# STM32F103C8T61.net
KiCad netlist of a schematic drawn in Altium Designer
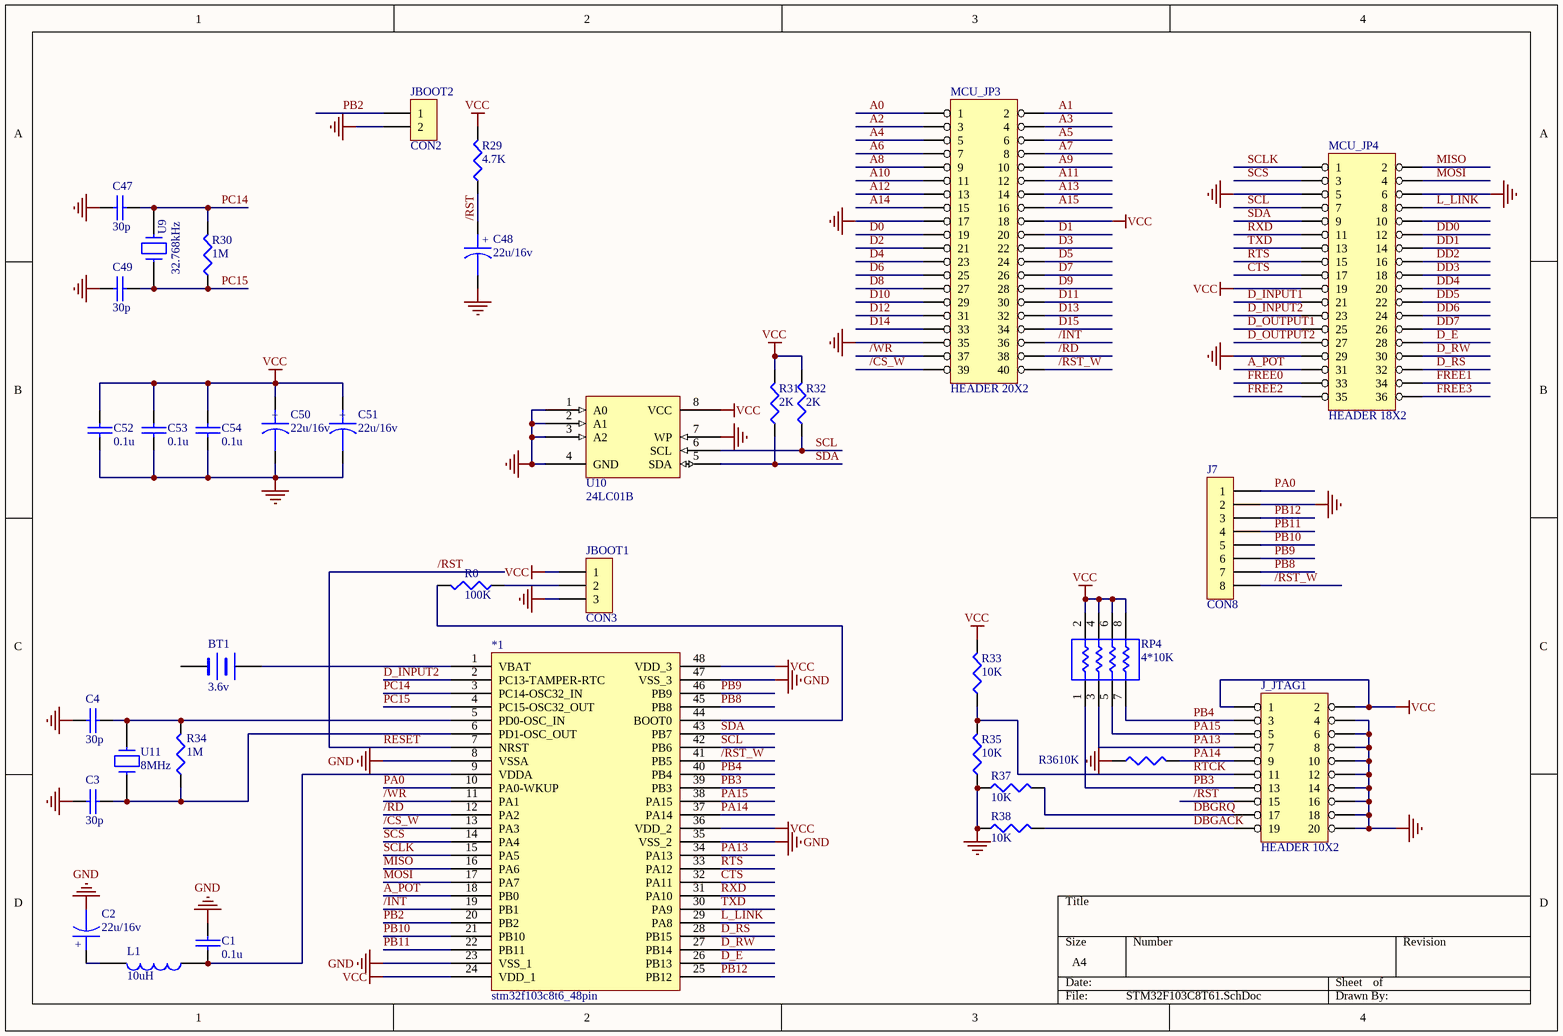
[diagram p0: STM32F103C8T61.SchDoc]

(export (version "E")
  (design (tool "Eeschema 10.0.6"))
  (components
    (comp (ref "*1") (value "stm32f103c8t6_48pin") (libsource (lib "stm32原理图库") (part "stm32f103c8t6_48pin")))
    (comp (ref "BT1")
      (value "3.6v")
      (footprint "BAT_JACK1")
      (description "Battery")
      (libsource (lib "*") (part "BATTERY"))
    )
    (comp (ref "C1")
      (value "0.1u")
      (footprint "0603")
      (description "Capacitor")
      (libsource (lib "*") (part "CAP"))
    )
    (comp (ref "C2")
      (value "22u/16v")
      (footprint "RB.1/.2N")
      (description "Capacitor")
      (libsource (lib "*") (part "CAPACITOR POL"))
    )
    (comp (ref "C3")
      (value "30p")
      (footprint "0603")
      (description "Capacitor")
      (libsource (lib "*") (part "CAP"))
    )
    (comp (ref "C4")
      (value "30p")
      (footprint "0603")
      (description "Capacitor")
      (libsource (lib "*") (part "CAP"))
    )
    (comp (ref "C47")
      (value "30p")
      (footprint "0603")
      (description "Capacitor")
      (libsource (lib "*") (part "CAP"))
    )
    (comp (ref "C48")
      (value "22u/16v")
      (footprint "RB.1/.2N")
      (description "Capacitor")
      (libsource (lib "*") (part "CAPACITOR POL"))
    )
    (comp (ref "C49")
      (value "30p")
      (footprint "0603")
      (description "Capacitor")
      (libsource (lib "*") (part "CAP"))
    )
    (comp (ref "C50")
      (value "22u/16v")
      (footprint "RB.1/.2N")
      (description "Capacitor")
      (libsource (lib "") (part "CAPACITOR POL_1"))
    )
    (comp (ref "C51")
      (value "22u/16v")
      (footprint "RB.1/.2N")
      (description "Capacitor")
      (libsource (lib "") (part "CAPACITOR POL_1"))
    )
    (comp (ref "C52")
      (value "0.1u")
      (footprint "0603")
      (description "Capacitor")
      (libsource (lib "*") (part "CAP"))
    )
    (comp (ref "C53")
      (value "0.1u")
      (footprint "0603")
      (description "Capacitor")
      (libsource (lib "*") (part "CAP"))
    )
    (comp (ref "C54")
      (value "0.1u")
      (footprint "0603")
      (description "Capacitor")
      (libsource (lib "*") (part "CAP"))
    )
    (comp (ref "J7")
      (value "CON8")
      (footprint "SIP8")
      (description "Connector")
      (libsource (lib "*") (part "CON8"))
    )
    (comp (ref "JBOOT1")
      (value "CON3")
      (footprint "SIP3")
      (description "Connector")
      (libsource (lib "*") (part "CON3"))
    )
    (comp (ref "JBOOT2")
      (value "CON2")
      (footprint "SIP2")
      (description "Connector")
      (libsource (lib "*") (part "CON2"))
    )
    (comp (ref "J_JTAG1")
      (value "HEADER 10X2")
      (footprint "IDC20")
      (libsource (lib "*") (part "HEADER 10X2"))
    )
    (comp (ref "L1") (value "10uH") (footprint "0603") (libsource (lib "*") (part "INDUCTOR")))
    (comp (ref "MCU_JP3")
      (value "HEADER 20X2")
      (footprint "IDC40-2")
      (libsource (lib "*") (part "HEADER 20X2"))
    )
    (comp (ref "MCU_JP4")
      (value "HEADER 18X2")
      (footprint "IDC36-2")
      (libsource (lib "*") (part "HEADER 18X2"))
    )
    (comp (ref "R0") (value "100K") (footprint "0603") (libsource (lib "*") (part "RES1")))
    (comp (ref "R29") (value "4.7K") (footprint "0603") (libsource (lib "*") (part "RES1")))
    (comp (ref "R30") (value "1M") (footprint "0603") (libsource (lib "*") (part "RES1")))
    (comp (ref "R31") (value "2K") (footprint "0603") (libsource (lib "*") (part "RES1")))
    (comp (ref "R32") (value "2K") (footprint "0603") (libsource (lib "*") (part "RES1")))
    (comp (ref "R33") (value "10K") (footprint "0603") (libsource (lib "*") (part "RES1")))
    (comp (ref "R34") (value "1M") (footprint "0603") (libsource (lib "*") (part "RES1")))
    (comp (ref "R35") (value "10K") (footprint "0603") (libsource (lib "*") (part "RES1")))
    (comp (ref "R36") (value "10K") (footprint "0603") (libsource (lib "*") (part "RES1")))
    (comp (ref "R37") (value "10K") (footprint "0603") (libsource (lib "*") (part "RES1")))
    (comp (ref "R38") (value "10K") (footprint "0603") (libsource (lib "*") (part "RES1")))
    (comp (ref "RP4")
      (value "4*10K")
      (footprint "4X0603")
      (description "RP?")
      (libsource (lib "*") (part "RES-4"))
    )
    (comp (ref "U9")
      (value "32.768kHz")
      (footprint "XTAL2")
      (description "Crystal")
      (libsource (lib "*") (part "CRYSTAL"))
    )
    (comp (ref "U10")
      (value "24LC01B")
      (footprint "DIP8")
      (description "24AA01")
      (libsource (lib "*") (part "24AA01"))
    )
    (comp (ref "U11")
      (value "8MHz")
      (footprint "XTAL")
      (description "Crystal")
      (libsource (lib "*") (part "CRYSTAL"))
    )
  )
  (nets
    (net (code "1") (name "/A0") (class "Default")
      (node (ref "MCU_JP3") (pin "1") (pinfunction "1_1") (pintype "passive"))
    )
    (net (code "2") (name "/A1") (class "Default")
      (node (ref "MCU_JP3") (pin "2") (pinfunction "2_2") (pintype "passive"))
    )
    (net (code "3") (name "/A2") (class "Default")
      (node (ref "MCU_JP3") (pin "3") (pinfunction "3_3") (pintype "passive"))
    )
    (net (code "4") (name "/A3") (class "Default")
      (node (ref "MCU_JP3") (pin "4") (pinfunction "4_4") (pintype "passive"))
    )
    (net (code "5") (name "/A4") (class "Default")
      (node (ref "MCU_JP3") (pin "5") (pinfunction "5_5") (pintype "passive"))
    )
    (net (code "6") (name "/A5") (class "Default")
      (node (ref "MCU_JP3") (pin "6") (pinfunction "6_6") (pintype "passive"))
    )
    (net (code "7") (name "/A6") (class "Default")
      (node (ref "MCU_JP3") (pin "7") (pinfunction "7_7") (pintype "passive"))
    )
    (net (code "8") (name "/A7") (class "Default")
      (node (ref "MCU_JP3") (pin "8") (pinfunction "8_8") (pintype "passive"))
    )
    (net (code "9") (name "/A8") (class "Default")
      (node (ref "MCU_JP3") (pin "9") (pinfunction "9_9") (pintype "passive"))
    )
    (net (code "10") (name "/A9") (class "Default")
      (node (ref "MCU_JP3") (pin "10") (pinfunction "10_10") (pintype "passive"))
    )
    (net (code "11") (name "/A10") (class "Default")
      (node (ref "MCU_JP3") (pin "11") (pinfunction "11_11") (pintype "passive"))
    )
    (net (code "12") (name "/A11") (class "Default")
      (node (ref "MCU_JP3") (pin "12") (pinfunction "12_12") (pintype "passive"))
    )
    (net (code "13") (name "/A12") (class "Default")
      (node (ref "MCU_JP3") (pin "13") (pinfunction "13_13") (pintype "passive"))
    )
    (net (code "14") (name "/A13") (class "Default")
      (node (ref "MCU_JP3") (pin "14") (pinfunction "14_14") (pintype "passive"))
    )
    (net (code "15") (name "/A14") (class "Default")
      (node (ref "MCU_JP3") (pin "15") (pinfunction "15_15") (pintype "passive"))
    )
    (net (code "16") (name "/A15") (class "Default")
      (node (ref "MCU_JP3") (pin "16") (pinfunction "16_16") (pintype "passive"))
    )
    (net (code "17") (name "/A_POT") (class "Default")
      (node (ref "*1") (pin "18") (pinfunction "PB0_18") (pintype "passive"))
      (node (ref "MCU_JP4") (pin "31") (pinfunction "31_31") (pintype "passive"))
    )
    (net (code "18") (name "/CTS") (class "Default")
      (node (ref "*1") (pin "32") (pinfunction "PA11_32") (pintype "passive"))
      (node (ref "MCU_JP4") (pin "17") (pinfunction "17_17") (pintype "passive"))
    )
    (net (code "19") (name "/D0") (class "Default")
      (node (ref "MCU_JP3") (pin "19") (pinfunction "19_19") (pintype "passive"))
    )
    (net (code "20") (name "/D1") (class "Default")
      (node (ref "MCU_JP3") (pin "20") (pinfunction "20_20") (pintype "passive"))
    )
    (net (code "21") (name "/D2") (class "Default")
      (node (ref "MCU_JP3") (pin "21") (pinfunction "21_21") (pintype "passive"))
    )
    (net (code "22") (name "/D3") (class "Default")
      (node (ref "MCU_JP3") (pin "22") (pinfunction "22_22") (pintype "passive"))
    )
    (net (code "23") (name "/D4") (class "Default")
      (node (ref "MCU_JP3") (pin "23") (pinfunction "23_23") (pintype "passive"))
    )
    (net (code "24") (name "/D5") (class "Default")
      (node (ref "MCU_JP3") (pin "24") (pinfunction "24_24") (pintype "passive"))
    )
    (net (code "25") (name "/D6") (class "Default")
      (node (ref "MCU_JP3") (pin "25") (pinfunction "25_25") (pintype "passive"))
    )
    (net (code "26") (name "/D7") (class "Default")
      (node (ref "MCU_JP3") (pin "26") (pinfunction "26_26") (pintype "passive"))
    )
    (net (code "27") (name "/D8") (class "Default")
      (node (ref "MCU_JP3") (pin "27") (pinfunction "27_27") (pintype "passive"))
    )
    (net (code "28") (name "/D9") (class "Default")
      (node (ref "MCU_JP3") (pin "28") (pinfunction "28_28") (pintype "passive"))
    )
    (net (code "29") (name "/D10") (class "Default")
      (node (ref "MCU_JP3") (pin "29") (pinfunction "29_29") (pintype "passive"))
    )
    (net (code "30") (name "/D11") (class "Default")
      (node (ref "MCU_JP3") (pin "30") (pinfunction "30_30") (pintype "passive"))
    )
    (net (code "31") (name "/D12") (class "Default")
      (node (ref "MCU_JP3") (pin "31") (pinfunction "31_31") (pintype "passive"))
    )
    (net (code "32") (name "/D13") (class "Default")
      (node (ref "MCU_JP3") (pin "32") (pinfunction "32_32") (pintype "passive"))
    )
    (net (code "33") (name "/D14") (class "Default")
      (node (ref "MCU_JP3") (pin "33") (pinfunction "33_33") (pintype "passive"))
    )
    (net (code "34") (name "/D15") (class "Default")
      (node (ref "MCU_JP3") (pin "34") (pinfunction "34_34") (pintype "passive"))
    )
    (net (code "35") (name "/DBGACK") (class "Default")
      (node (ref "J_JTAG1") (pin "19") (pinfunction "19_19") (pintype "passive"))
      (node (ref "R38") (pin "2") (pinfunction "2_2") (pintype "passive"))
    )
    (net (code "36") (name "/DBGRQ") (class "Default")
      (node (ref "J_JTAG1") (pin "17") (pinfunction "17_17") (pintype "passive"))
      (node (ref "R37") (pin "2") (pinfunction "2_2") (pintype "passive"))
    )
    (net (code "37") (name "/DD0") (class "Default")
      (node (ref "MCU_JP4") (pin "12") (pinfunction "12_12") (pintype "passive"))
    )
    (net (code "38") (name "/DD1") (class "Default")
      (node (ref "MCU_JP4") (pin "14") (pinfunction "14_14") (pintype "passive"))
    )
    (net (code "39") (name "/DD2") (class "Default")
      (node (ref "MCU_JP4") (pin "16") (pinfunction "16_16") (pintype "passive"))
    )
    (net (code "40") (name "/DD3") (class "Default")
      (node (ref "MCU_JP4") (pin "18") (pinfunction "18_18") (pintype "passive"))
    )
    (net (code "41") (name "/DD4") (class "Default")
      (node (ref "MCU_JP4") (pin "20") (pinfunction "20_20") (pintype "passive"))
    )
    (net (code "42") (name "/DD5") (class "Default")
      (node (ref "MCU_JP4") (pin "22") (pinfunction "22_22") (pintype "passive"))
    )
    (net (code "43") (name "/DD6") (class "Default")
      (node (ref "MCU_JP4") (pin "24") (pinfunction "24_24") (pintype "passive"))
    )
    (net (code "44") (name "/DD7") (class "Default")
      (node (ref "MCU_JP4") (pin "26") (pinfunction "26_26") (pintype "passive"))
    )
    (net (code "45") (name "/D_E") (class "Default")
      (node (ref "*1") (pin "26") (pinfunction "PB13_26") (pintype "passive"))
      (node (ref "MCU_JP4") (pin "28") (pinfunction "28_28") (pintype "passive"))
    )
    (net (code "46") (name "/D_INPUT1") (class "Default")
      (node (ref "MCU_JP4") (pin "21") (pinfunction "21_21") (pintype "passive"))
    )
    (net (code "47") (name "/D_INPUT2") (class "Default")
      (node (ref "*1") (pin "2") (pinfunction "PC13-TAMPER-RTC_2") (pintype "passive"))
      (node (ref "MCU_JP4") (pin "23") (pinfunction "23_23") (pintype "passive"))
    )
    (net (code "48") (name "/D_OUTPUT1") (class "Default")
      (node (ref "MCU_JP4") (pin "25") (pinfunction "25_25") (pintype "passive"))
    )
    (net (code "49") (name "/D_OUTPUT2") (class "Default")
      (node (ref "MCU_JP4") (pin "27") (pinfunction "27_27") (pintype "passive"))
    )
    (net (code "50") (name "/D_RS") (class "Default")
      (node (ref "*1") (pin "28") (pinfunction "PB15_28") (pintype "passive"))
      (node (ref "MCU_JP4") (pin "32") (pinfunction "32_32") (pintype "passive"))
    )
    (net (code "51") (name "/D_RW") (class "Default")
      (node (ref "*1") (pin "27") (pinfunction "PB14_27") (pintype "passive"))
      (node (ref "MCU_JP4") (pin "30") (pinfunction "30_30") (pintype "passive"))
    )
    (net (code "52") (name "/FREE0") (class "Default")
      (node (ref "MCU_JP4") (pin "33") (pinfunction "33_33") (pintype "passive"))
    )
    (net (code "53") (name "/FREE1") (class "Default")
      (node (ref "MCU_JP4") (pin "34") (pinfunction "34_34") (pintype "passive"))
    )
    (net (code "54") (name "/FREE2") (class "Default")
      (node (ref "MCU_JP4") (pin "35") (pinfunction "35_35") (pintype "passive"))
    )
    (net (code "55") (name "/FREE3") (class "Default")
      (node (ref "MCU_JP4") (pin "36") (pinfunction "36_36") (pintype "passive"))
    )
    (net (code "56") (name "/L_LINK") (class "Default")
      (node (ref "*1") (pin "29") (pinfunction "PA8_29") (pintype "passive"))
      (node (ref "MCU_JP4") (pin "8") (pinfunction "8_8") (pintype "passive"))
    )
    (net (code "57") (name "/MISO") (class "Default")
      (node (ref "*1") (pin "16") (pinfunction "PA6_16") (pintype "passive"))
      (node (ref "MCU_JP4") (pin "2") (pinfunction "2_2") (pintype "passive"))
    )
    (net (code "58") (name "/MOSI") (class "Default")
      (node (ref "*1") (pin "17") (pinfunction "PA7_17") (pintype "passive"))
      (node (ref "MCU_JP4") (pin "4") (pinfunction "4_4") (pintype "passive"))
    )
    (net (code "59") (name "/PA0") (class "Default")
      (node (ref "*1") (pin "10") (pinfunction "PA0-WKUP_10") (pintype "passive"))
      (node (ref "J7") (pin "1") (pinfunction "1_1") (pintype "passive"))
    )
    (net (code "60") (name "/PA13") (class "Default")
      (node (ref "*1") (pin "34") (pinfunction "PA13_34") (pintype "passive"))
      (node (ref "J_JTAG1") (pin "7") (pinfunction "7_7") (pintype "passive"))
      (node (ref "RP4") (pin "3") (pinfunction "3_3") (pintype "passive"))
    )
    (net (code "61") (name "/PA14") (class "Default")
      (node (ref "*1") (pin "37") (pinfunction "PA14_37") (pintype "passive"))
      (node (ref "J_JTAG1") (pin "9") (pinfunction "9_9") (pintype "passive"))
      (node (ref "R36") (pin "2") (pinfunction "2_2") (pintype "passive"))
    )
    (net (code "62") (name "/PA15") (class "Default")
      (node (ref "*1") (pin "38") (pinfunction "PA15_38") (pintype "passive"))
      (node (ref "J_JTAG1") (pin "5") (pinfunction "5_5") (pintype "passive"))
      (node (ref "RP4") (pin "5") (pinfunction "5_5") (pintype "passive"))
    )
    (net (code "63") (name "/PB2") (class "Default")
      (node (ref "*1") (pin "20") (pinfunction "PB2_20") (pintype "passive"))
      (node (ref "JBOOT2") (pin "1") (pinfunction "1_1") (pintype "passive"))
    )
    (net (code "64") (name "/PB3") (class "Default")
      (node (ref "*1") (pin "39") (pinfunction "PB3_39") (pintype "passive"))
      (node (ref "J_JTAG1") (pin "13") (pinfunction "13_13") (pintype "passive"))
      (node (ref "RP4") (pin "1") (pinfunction "1_1") (pintype "passive"))
    )
    (net (code "65") (name "/PB4") (class "Default")
      (node (ref "*1") (pin "40") (pinfunction "PB4_40") (pintype "passive"))
      (node (ref "J_JTAG1") (pin "3") (pinfunction "3_3") (pintype "passive"))
      (node (ref "RP4") (pin "7") (pinfunction "7_7") (pintype "passive"))
    )
    (net (code "66") (name "/PB8") (class "Default")
      (node (ref "*1") (pin "45") (pinfunction "PB8_45") (pintype "passive"))
      (node (ref "J7") (pin "7") (pinfunction "7_7") (pintype "passive"))
    )
    (net (code "67") (name "/PB9") (class "Default")
      (node (ref "*1") (pin "46") (pinfunction "PB9_46") (pintype "passive"))
      (node (ref "J7") (pin "6") (pinfunction "6_6") (pintype "passive"))
    )
    (net (code "68") (name "/PB10") (class "Default")
      (node (ref "*1") (pin "21") (pinfunction "PB10_21") (pintype "passive"))
      (node (ref "J7") (pin "5") (pinfunction "5_5") (pintype "passive"))
    )
    (net (code "69") (name "/PB11") (class "Default")
      (node (ref "*1") (pin "22") (pinfunction "PB11_22") (pintype "passive"))
      (node (ref "J7") (pin "4") (pinfunction "4_4") (pintype "passive"))
    )
    (net (code "70") (name "/PB12") (class "Default")
      (node (ref "*1") (pin "25") (pinfunction "PB12_25") (pintype "passive"))
      (node (ref "J7") (pin "3") (pinfunction "3_3") (pintype "passive"))
    )
    (net (code "71") (name "/PC14") (class "Default")
      (node (ref "*1") (pin "3") (pinfunction "PC14-OSC32_IN_3") (pintype "passive"))
      (node (ref "C47") (pin "1") (pinfunction "1_1") (pintype "passive"))
      (node (ref "R30") (pin "2") (pinfunction "2_2") (pintype "passive"))
      (node (ref "U9") (pin "1") (pinfunction "1_1") (pintype "passive"))
    )
    (net (code "72") (name "/PC15") (class "Default")
      (node (ref "*1") (pin "4") (pinfunction "PC15-OSC32_OUT_4") (pintype "passive"))
      (node (ref "C49") (pin "1") (pinfunction "1_1") (pintype "passive"))
      (node (ref "R30") (pin "1") (pinfunction "1_1") (pintype "passive"))
      (node (ref "U9") (pin "2") (pinfunction "2_2") (pintype "passive"))
    )
    (net (code "73") (name "/RESET") (class "Default")
      (node (ref "*1") (pin "7") (pinfunction "NRST_7") (pintype "passive"))
      (node (ref "C48") (pin "1") (pinfunction "1_1") (pintype "passive"))
      (node (ref "J_JTAG1") (pin "15") (pinfunction "15_15") (pintype "passive"))
      (node (ref "R29") (pin "1") (pinfunction "1_1") (pintype "passive"))
    )
    (net (code "74") (name "/RTCK") (class "Default")
      (node (ref "J_JTAG1") (pin "11") (pinfunction "11_11") (pintype "passive"))
      (node (ref "R33") (pin "1") (pinfunction "1_1") (pintype "passive"))
      (node (ref "R35") (pin "2") (pinfunction "2_2") (pintype "passive"))
    )
    (net (code "75") (name "/RTS") (class "Default")
      (node (ref "*1") (pin "33") (pinfunction "PA12_33") (pintype "passive"))
      (node (ref "MCU_JP4") (pin "15") (pinfunction "15_15") (pintype "passive"))
    )
    (net (code "76") (name "/RXD") (class "Default")
      (node (ref "*1") (pin "31") (pinfunction "PA10_31") (pintype "passive"))
      (node (ref "MCU_JP4") (pin "11") (pinfunction "11_11") (pintype "passive"))
    )
    (net (code "77") (name "/SCL") (class "Default")
      (node (ref "*1") (pin "42") (pinfunction "PB6_42") (pintype "passive"))
      (node (ref "MCU_JP4") (pin "7") (pinfunction "7_7") (pintype "passive"))
      (node (ref "R32") (pin "1") (pinfunction "1_1") (pintype "passive"))
      (node (ref "U10") (pin "6") (pinfunction "SCL_6") (pintype "input"))
    )
    (net (code "78") (name "/SCLK") (class "Default")
      (node (ref "*1") (pin "15") (pinfunction "PA5_15") (pintype "passive"))
      (node (ref "MCU_JP4") (pin "1") (pinfunction "1_1") (pintype "passive"))
    )
    (net (code "79") (name "/SCS") (class "Default")
      (node (ref "*1") (pin "14") (pinfunction "PA4_14") (pintype "passive"))
      (node (ref "MCU_JP4") (pin "3") (pinfunction "3_3") (pintype "passive"))
    )
    (net (code "80") (name "/SDA") (class "Default")
      (node (ref "*1") (pin "43") (pinfunction "PB7_43") (pintype "passive"))
      (node (ref "MCU_JP4") (pin "9") (pinfunction "9_9") (pintype "passive"))
      (node (ref "R31") (pin "1") (pinfunction "1_1") (pintype "passive"))
      (node (ref "U10") (pin "5") (pinfunction "SDA_5") (pintype "bidirectional"))
    )
    (net (code "81") (name "/TXD") (class "Default")
      (node (ref "*1") (pin "30") (pinfunction "PA9_30") (pintype "passive"))
      (node (ref "MCU_JP4") (pin "13") (pinfunction "13_13") (pintype "passive"))
    )
    (net (code "82") (name "/{slash}CS_W") (class "Default")
      (node (ref "*1") (pin "13") (pinfunction "PA3_13") (pintype "passive"))
      (node (ref "MCU_JP3") (pin "39") (pinfunction "39_39") (pintype "passive"))
    )
    (net (code "83") (name "/{slash}INT") (class "Default")
      (node (ref "*1") (pin "19") (pinfunction "PB1_19") (pintype "passive"))
      (node (ref "MCU_JP3") (pin "36") (pinfunction "36_36") (pintype "passive"))
    )
    (net (code "84") (name "/{slash}RD") (class "Default")
      (node (ref "*1") (pin "12") (pinfunction "PA2_12") (pintype "passive"))
      (node (ref "MCU_JP3") (pin "38") (pinfunction "38_38") (pintype "passive"))
    )
    (net (code "85") (name "/{slash}RST_W") (class "Default")
      (node (ref "*1") (pin "41") (pinfunction "PB5_41") (pintype "passive"))
      (node (ref "J7") (pin "8") (pinfunction "8_8") (pintype "passive"))
      (node (ref "MCU_JP3") (pin "40") (pinfunction "40_40") (pintype "passive"))
    )
    (net (code "86") (name "/{slash}WR") (class "Default")
      (node (ref "*1") (pin "11") (pinfunction "PA1_11") (pintype "passive"))
      (node (ref "MCU_JP3") (pin "37") (pinfunction "37_37") (pintype "passive"))
    )
    (net (code "87") (name "GND") (class "Default")
      (node (ref "*1") (pin "23") (pinfunction "VSS_1_23") (pintype "passive"))
      (node (ref "*1") (pin "35") (pinfunction "VSS_2_35") (pintype "passive"))
      (node (ref "*1") (pin "47") (pinfunction "VSS_3_47") (pintype "passive"))
      (node (ref "*1") (pin "8") (pinfunction "VSSA_8") (pintype "passive"))
      (node (ref "C1") (pin "2") (pinfunction "2_2") (pintype "passive"))
      (node (ref "C3") (pin "2") (pinfunction "2_2") (pintype "passive"))
      (node (ref "C4") (pin "2") (pinfunction "2_2") (pintype "passive"))
      (node (ref "C47") (pin "2") (pinfunction "2_2") (pintype "passive"))
      (node (ref "C48") (pin "2") (pinfunction "2_2") (pintype "passive"))
      (node (ref "C49") (pin "2") (pinfunction "2_2") (pintype "passive"))
      (node (ref "C50") (pin "2") (pinfunction "2_2") (pintype "passive"))
      (node (ref "C51") (pin "2") (pinfunction "2_2") (pintype "passive"))
      (node (ref "C52") (pin "2") (pinfunction "2_2") (pintype "passive"))
      (node (ref "C53") (pin "1") (pinfunction "1_1") (pintype "passive"))
      (node (ref "C54") (pin "1") (pinfunction "1_1") (pintype "passive"))
      (node (ref "J7") (pin "2") (pinfunction "2_2") (pintype "passive"))
      (node (ref "JBOOT1") (pin "3") (pinfunction "3_3") (pintype "passive"))
      (node (ref "JBOOT2") (pin "2") (pinfunction "2_2") (pintype "passive"))
      (node (ref "J_JTAG1") (pin "10") (pinfunction "10_10") (pintype "passive"))
      (node (ref "J_JTAG1") (pin "12") (pinfunction "12_12") (pintype "passive"))
      (node (ref "J_JTAG1") (pin "14") (pinfunction "14_14") (pintype "passive"))
      (node (ref "J_JTAG1") (pin "16") (pinfunction "16_16") (pintype "passive"))
      (node (ref "J_JTAG1") (pin "18") (pinfunction "18_18") (pintype "passive"))
      (node (ref "J_JTAG1") (pin "20") (pinfunction "20_20") (pintype "passive"))
      (node (ref "J_JTAG1") (pin "4") (pinfunction "4_4") (pintype "passive"))
      (node (ref "J_JTAG1") (pin "6") (pinfunction "6_6") (pintype "passive"))
      (node (ref "J_JTAG1") (pin "8") (pinfunction "8_8") (pintype "passive"))
      (node (ref "MCU_JP3") (pin "17") (pinfunction "17_17") (pintype "passive"))
      (node (ref "MCU_JP3") (pin "35") (pinfunction "35_35") (pintype "passive"))
      (node (ref "MCU_JP4") (pin "29") (pinfunction "29_29") (pintype "passive"))
      (node (ref "MCU_JP4") (pin "5") (pinfunction "5_5") (pintype "passive"))
      (node (ref "MCU_JP4") (pin "6") (pinfunction "6_6") (pintype "passive"))
      (node (ref "R35") (pin "1") (pinfunction "1_1") (pintype "passive"))
      (node (ref "R36") (pin "1") (pinfunction "1_1") (pintype "passive"))
      (node (ref "R37") (pin "1") (pinfunction "1_1") (pintype "passive"))
      (node (ref "R38") (pin "1") (pinfunction "1_1") (pintype "passive"))
      (node (ref "U10") (pin "1") (pinfunction "A0_1") (pintype "input"))
      (node (ref "U10") (pin "2") (pinfunction "A1_2") (pintype "input"))
      (node (ref "U10") (pin "3") (pinfunction "A2_3") (pintype "input"))
      (node (ref "U10") (pin "4") (pinfunction "GND_4") (pintype "power_in"))
      (node (ref "U10") (pin "7") (pinfunction "WP_7") (pintype "input"))
    )
    (net (code "88") (name "Net-(*1-BOOT0)") (class "Default")
      (node (ref "*1") (pin "44") (pinfunction "BOOT0_44") (pintype "passive"))
      (node (ref "R0") (pin "2") (pinfunction "2_2") (pintype "passive"))
    )
    (net (code "89") (name "Net-(*1-PD0-OSC_IN)") (class "Default")
      (node (ref "*1") (pin "5") (pinfunction "PD0-OSC_IN_5") (pintype "passive"))
      (node (ref "C4") (pin "1") (pinfunction "1_1") (pintype "passive"))
      (node (ref "R34") (pin "1") (pinfunction "1_1") (pintype "passive"))
      (node (ref "U11") (pin "2") (pinfunction "2_2") (pintype "passive"))
    )
    (net (code "90") (name "Net-(*1-PD1-OSC_OUT)") (class "Default")
      (node (ref "*1") (pin "6") (pinfunction "PD1-OSC_OUT_6") (pintype "passive"))
      (node (ref "C3") (pin "1") (pinfunction "1_1") (pintype "passive"))
      (node (ref "R34") (pin "2") (pinfunction "2_2") (pintype "passive"))
      (node (ref "U11") (pin "1") (pinfunction "1_1") (pintype "passive"))
    )
    (net (code "91") (name "Net-(*1-VBAT)") (class "Default")
      (node (ref "*1") (pin "1") (pinfunction "VBAT_1") (pintype "passive"))
      (node (ref "BT1") (pin "1") (pinfunction "+_1") (pintype "passive"))
    )
    (net (code "92") (name "Net-(*1-VDDA)") (class "Default")
      (node (ref "*1") (pin "9") (pinfunction "VDDA_9") (pintype "passive"))
      (node (ref "C1") (pin "1") (pinfunction "1_1") (pintype "passive"))
      (node (ref "L1") (pin "1") (pinfunction "1_1") (pintype "passive"))
    )
    (net (code "93") (name "Net-(C2-Pad1)") (class "Default")
      (node (ref "C2") (pin "1") (pinfunction "1_1") (pintype "passive"))
      (node (ref "L1") (pin "2") (pinfunction "2_2") (pintype "passive"))
    )
    (net (code "94") (name "Net-(JBOOT1-Pad2)") (class "Default")
      (node (ref "JBOOT1") (pin "2") (pinfunction "2_2") (pintype "passive"))
      (node (ref "R0") (pin "1") (pinfunction "1_1") (pintype "passive"))
    )
    (net (code "95") (name "VCC") (class "Default")
      (node (ref "*1") (pin "24") (pinfunction "VDD_1_24") (pintype "passive"))
      (node (ref "*1") (pin "36") (pinfunction "VDD_2_36") (pintype "passive"))
      (node (ref "*1") (pin "48") (pinfunction "VDD_3_48") (pintype "passive"))
      (node (ref "C50") (pin "1") (pinfunction "1_1") (pintype "passive"))
      (node (ref "C51") (pin "1") (pinfunction "1_1") (pintype "passive"))
      (node (ref "C52") (pin "1") (pinfunction "1_1") (pintype "passive"))
      (node (ref "C53") (pin "2") (pinfunction "2_2") (pintype "passive"))
      (node (ref "C54") (pin "2") (pinfunction "2_2") (pintype "passive"))
      (node (ref "JBOOT1") (pin "1") (pinfunction "1_1") (pintype "passive"))
      (node (ref "J_JTAG1") (pin "1") (pinfunction "1_1") (pintype "passive"))
      (node (ref "J_JTAG1") (pin "2") (pinfunction "2_2") (pintype "passive"))
      (node (ref "MCU_JP3") (pin "18") (pinfunction "18_18") (pintype "passive"))
      (node (ref "MCU_JP4") (pin "19") (pinfunction "19_19") (pintype "passive"))
      (node (ref "R29") (pin "2") (pinfunction "2_2") (pintype "passive"))
      (node (ref "R31") (pin "2") (pinfunction "2_2") (pintype "passive"))
      (node (ref "R32") (pin "2") (pinfunction "2_2") (pintype "passive"))
      (node (ref "R33") (pin "2") (pinfunction "2_2") (pintype "passive"))
      (node (ref "RP4") (pin "2") (pinfunction "2_2") (pintype "passive"))
      (node (ref "RP4") (pin "4") (pinfunction "4_4") (pintype "passive"))
      (node (ref "RP4") (pin "6") (pinfunction "6_6") (pintype "passive"))
      (node (ref "RP4") (pin "8") (pinfunction "8_8") (pintype "passive"))
      (node (ref "U10") (pin "8") (pinfunction "VCC_8") (pintype "power_in"))
    )
    (net (code "96") (name "unconnected-(BT1---Pad2)") (class "Default")
      (node (ref "BT1") (pin "2") (pinfunction "-_2") (pintype "passive"))
    )
    (net (code "97") (name "unconnected-(C2-Pad2)") (class "Default")
      (node (ref "C2") (pin "2") (pinfunction "2_2") (pintype "passive"))
    )
    (net (code "98") (name "unconnected-(MCU_JP4-Pad10)") (class "Default")
      (node (ref "MCU_JP4") (pin "10") (pinfunction "10_10") (pintype "passive"))
    )
  )
)
